# Power.net
KiCad netlist of a schematic drawn in Altium Designer
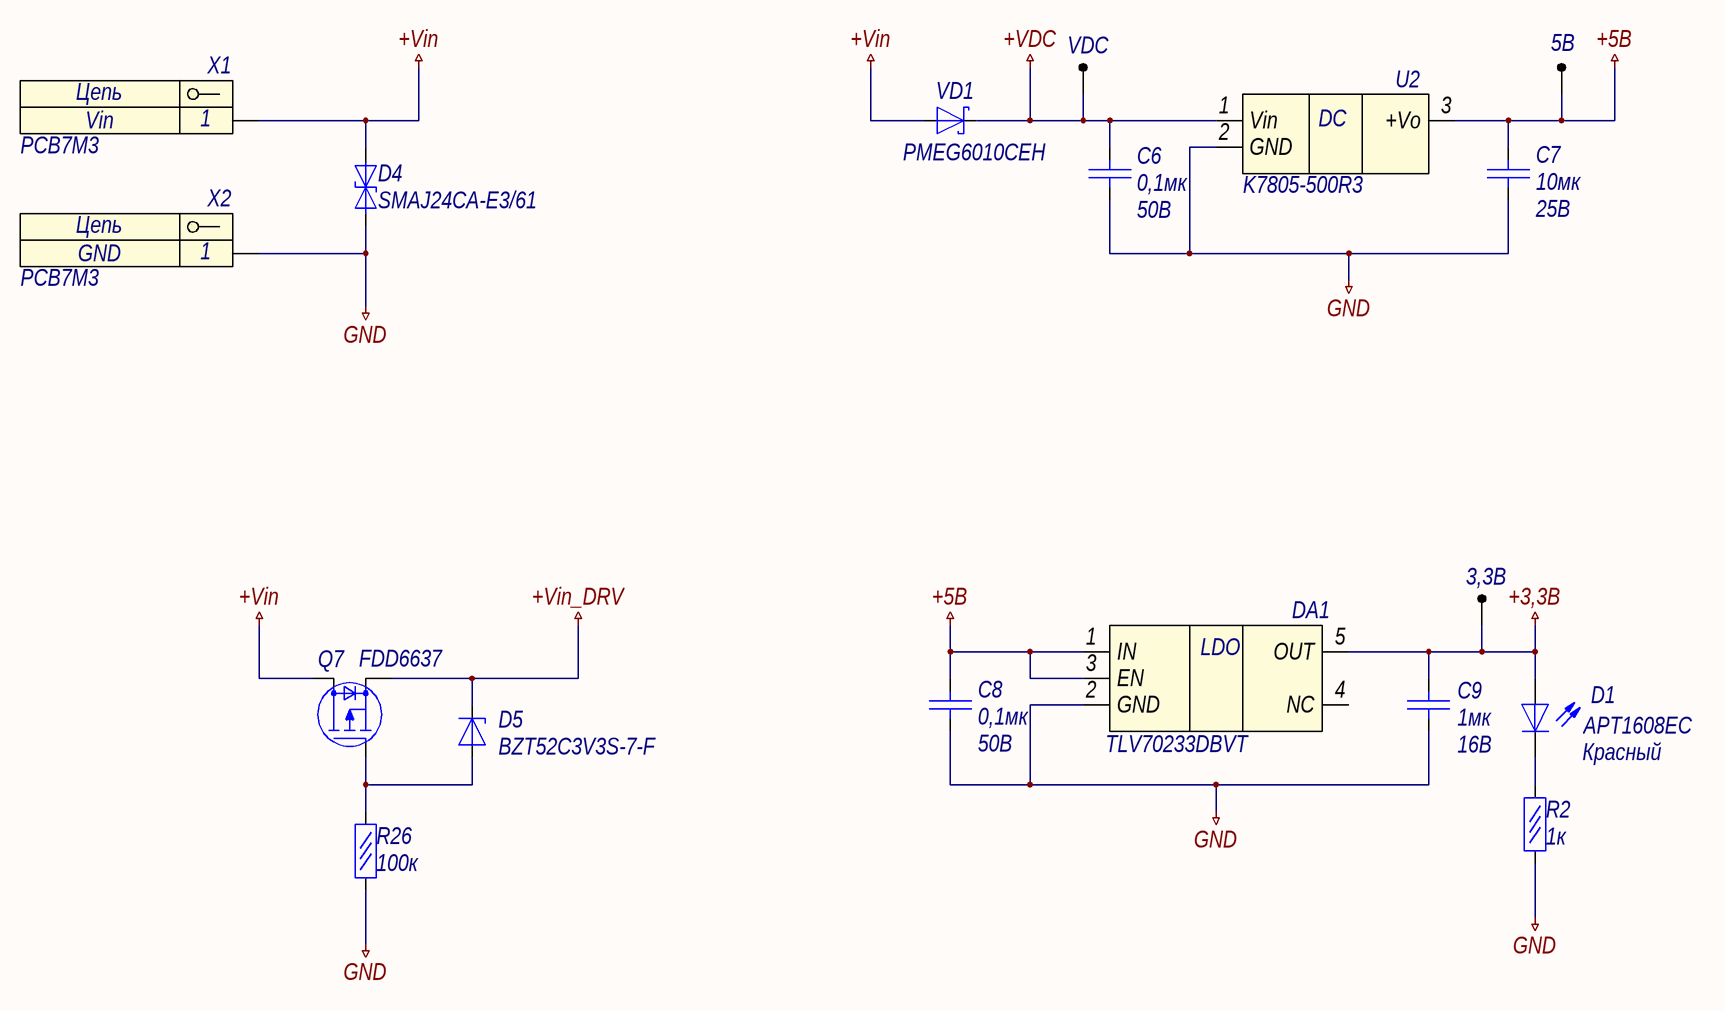
[diagram p0: Power.SchDoc]

(export (version "E")
  (design (tool "Eeschema 10.0.6"))
  (components
    (comp (ref "3,3В")
      (value "\"1\"")
      (footprint "0.5 x 1_round")
      (description "Test point")
      (libsource (lib "TarabusLib_KOR") (part "TestPoint"))
    )
    (comp (ref "5В")
      (value "\"1\"")
      (footprint "0.5 x 1_round")
      (description "Test point")
      (libsource (lib "TarabusLib_KOR") (part "TestPoint"))
    )
    (comp (ref "C6")
      (value "0,1мк")
      (footprint "C0805_AA")
      (description "Конденсатор кер.")
      (fields (field (name "VOLTAGE") "50В"))
      (libsource (lib "Library_Diana") (part "Конденсатор кер."))
    )
    (comp (ref "C7")
      (value "10мк")
      (footprint "C0805_AA")
      (description "Конденсатор кер.")
      (fields (field (name "VOLTAGE") "25В"))
      (libsource (lib "Library_Diana") (part "Конденсатор кер."))
    )
    (comp (ref "C8")
      (value "0,1мк")
      (footprint "C0805_AA")
      (description "Конденсатор кер.")
      (fields (field (name "VOLTAGE") "50В"))
      (libsource (lib "Library_Diana") (part "Конденсатор кер."))
    )
    (comp (ref "C9")
      (value "1мк")
      (footprint "C0805_AA")
      (description "Конденсатор кер.")
      (fields (field (name "VOLTAGE") "16В"))
      (libsource (lib "Library_Diana") (part "Конденсатор кер."))
    )
    (comp (ref "D1")
      (value "APT1608EC")
      (footprint "D0603_A")
      (description "Светодиод")
      (fields (field (name "VR") "Красный"))
      (libsource (lib "Library_Diana") (part "LED_R"))
    )
    (comp (ref "D4")
      (value "SMAJ24CA-E3/61")
      (description "Ограничитель напряжения односторонний")
      (fields (field (name "NAME") "SMAJ24CA-E3/61"))
      (libsource (lib "Library_Diana") (part "diode-2tvs"))
    )
    (comp (ref "D5")
      (value "BZT52C3V3S-7-F")
      (footprint "SOT23-2_A")
      (description "Стабилитрон")
      (libsource (lib "Library_Diana") (part "DiodeZener"))
    )
    (comp (ref "DA1")
      (value "TLV70233DBVT")
      (description "LDO Regulator")
      (libsource (lib "Library_Diana") (part "TLV702"))
    )
    (comp (ref "Q7")
      (value "FDD6637")
      (footprint "SOT23-3_A")
      (description "P-MOSFET")
      (libsource (lib "Library_Diana") (part "P-MOSFET"))
    )
    (comp (ref "R2")
      (value "1к")
      (footprint "R1206")
      (description "Резистор 0,05Вт")
      (libsource (lib "Library_Diana") (part "Резистор  0,05Вт"))
    )
    (comp (ref "R26")
      (value "100к")
      (footprint "R1206")
      (description "Резистор 0,05Вт")
      (libsource (lib "Library_Diana") (part "Резистор  0,05Вт"))
    )
    (comp (ref "U2")
      (value "K7805-500R3")
      (description "DC/DC преобразователь неизолированный")
      (libsource (lib "Library_Diana") (part "K78xx-500R3"))
    )
    (comp (ref "VD1")
      (value "PMEG6010CEH")
      (footprint "SOD123_A")
      (description "Диод Шоттки")
      (libsource (lib "Library_Diana") (part "DiodeSchottky"))
    )
    (comp (ref "VDC")
      (value "\"1\"")
      (footprint "0.5 x 1_round")
      (description "Test point")
      (libsource (lib "TarabusLib_KOR") (part "TestPoint"))
    )
    (comp (ref "X1")
      (value "PCB7M3")
      (description "Разъем - 1 конт. клемма")
      (fields (field (name "NAME") "PCB7M3"))
      (libsource (lib "Library_Diana") (part "x1-k"))
    )
    (comp (ref "X2")
      (value "PCB7M3")
      (description "Разъем - 1 конт. клемма")
      (fields (field (name "NAME") "PCB7M3"))
      (libsource (lib "Library_Diana") (part "x1-k"))
    )
  )
  (nets
    (net (code "1") (name "+3,3В") (class "Default")
      (node (ref "3,3В") (pin "1") (pinfunction "1_1") (pintype "passive"))
      (node (ref "C9") (pin "2") (pinfunction "2_2") (pintype "passive"))
      (node (ref "D1") (pin "1") (pinfunction "Анод_1") (pintype "passive"))
      (node (ref "DA1") (pin "5") (pinfunction "OUT_5") (pintype "passive"))
    )
    (net (code "2") (name "+5В") (class "Default")
      (node (ref "5В") (pin "1") (pinfunction "1_1") (pintype "passive"))
      (node (ref "C7") (pin "2") (pinfunction "2_2") (pintype "passive"))
      (node (ref "C8") (pin "2") (pinfunction "2_2") (pintype "passive"))
      (node (ref "DA1") (pin "1") (pinfunction "IN_1") (pintype "passive"))
      (node (ref "DA1") (pin "3") (pinfunction "EN_3") (pintype "passive"))
      (node (ref "U2") (pin "3") (pinfunction "+Vo_3") (pintype "power_in"))
    )
    (net (code "3") (name "+VDC") (class "Default")
      (node (ref "C6") (pin "2") (pinfunction "2_2") (pintype "passive"))
      (node (ref "U2") (pin "1") (pinfunction "Vin_1") (pintype "power_in"))
      (node (ref "VD1") (pin "1") (pinfunction "K_1") (pintype "passive"))
      (node (ref "VDC") (pin "1") (pinfunction "1_1") (pintype "passive"))
    )
    (net (code "4") (name "+Vin") (class "Default")
      (node (ref "D4") (pin "2") (pinfunction "K_2") (pintype "passive"))
      (node (ref "Q7") (pin "3") (pinfunction "D_3") (pintype "passive"))
      (node (ref "VD1") (pin "2") (pinfunction "A_2") (pintype "passive"))
      (node (ref "X1") (pin "1") (pinfunction "1_1") (pintype "passive"))
    )
    (net (code "5") (name "+Vin_DRV") (class "Default")
      (node (ref "D5") (pin "1") (pinfunction "K_1") (pintype "passive"))
      (node (ref "Q7") (pin "2") (pinfunction "S_2") (pintype "passive"))
    )
    (net (code "6") (name "GND") (class "Default")
      (node (ref "C6") (pin "1") (pinfunction "1_1") (pintype "passive"))
      (node (ref "C7") (pin "1") (pinfunction "1_1") (pintype "passive"))
      (node (ref "C8") (pin "1") (pinfunction "1_1") (pintype "passive"))
      (node (ref "C9") (pin "1") (pinfunction "1_1") (pintype "passive"))
      (node (ref "D4") (pin "1") (pinfunction "A_1") (pintype "passive"))
      (node (ref "DA1") (pin "2") (pinfunction "GND_2") (pintype "passive"))
      (node (ref "R2") (pin "1") (pinfunction "1_1") (pintype "passive"))
      (node (ref "R26") (pin "1") (pinfunction "1_1") (pintype "passive"))
      (node (ref "U2") (pin "2") (pinfunction "GND_2") (pintype "power_in"))
      (node (ref "X2") (pin "1") (pinfunction "1_1") (pintype "passive"))
    )
    (net (code "7") (name "Net-(D1-Катод)") (class "Default")
      (node (ref "D1") (pin "2") (pinfunction "Катод_2") (pintype "passive"))
      (node (ref "R2") (pin "2") (pinfunction "2_2") (pintype "passive"))
    )
    (net (code "8") (name "Net-(D5-A)") (class "Default")
      (node (ref "D5") (pin "2") (pinfunction "A_2") (pintype "passive"))
      (node (ref "Q7") (pin "1") (pinfunction "G_1") (pintype "passive"))
      (node (ref "R26") (pin "2") (pinfunction "2_2") (pintype "passive"))
    )
    (net (code "9") (name "unconnected-(DA1-NC-Pad4)") (class "Default")
      (node (ref "DA1") (pin "4") (pinfunction "NC_4") (pintype "passive"))
    )
  )
)
